# FlexEMG_v0r0_SF2-COMM.net
KiCad netlist of a schematic drawn in Altium Designer
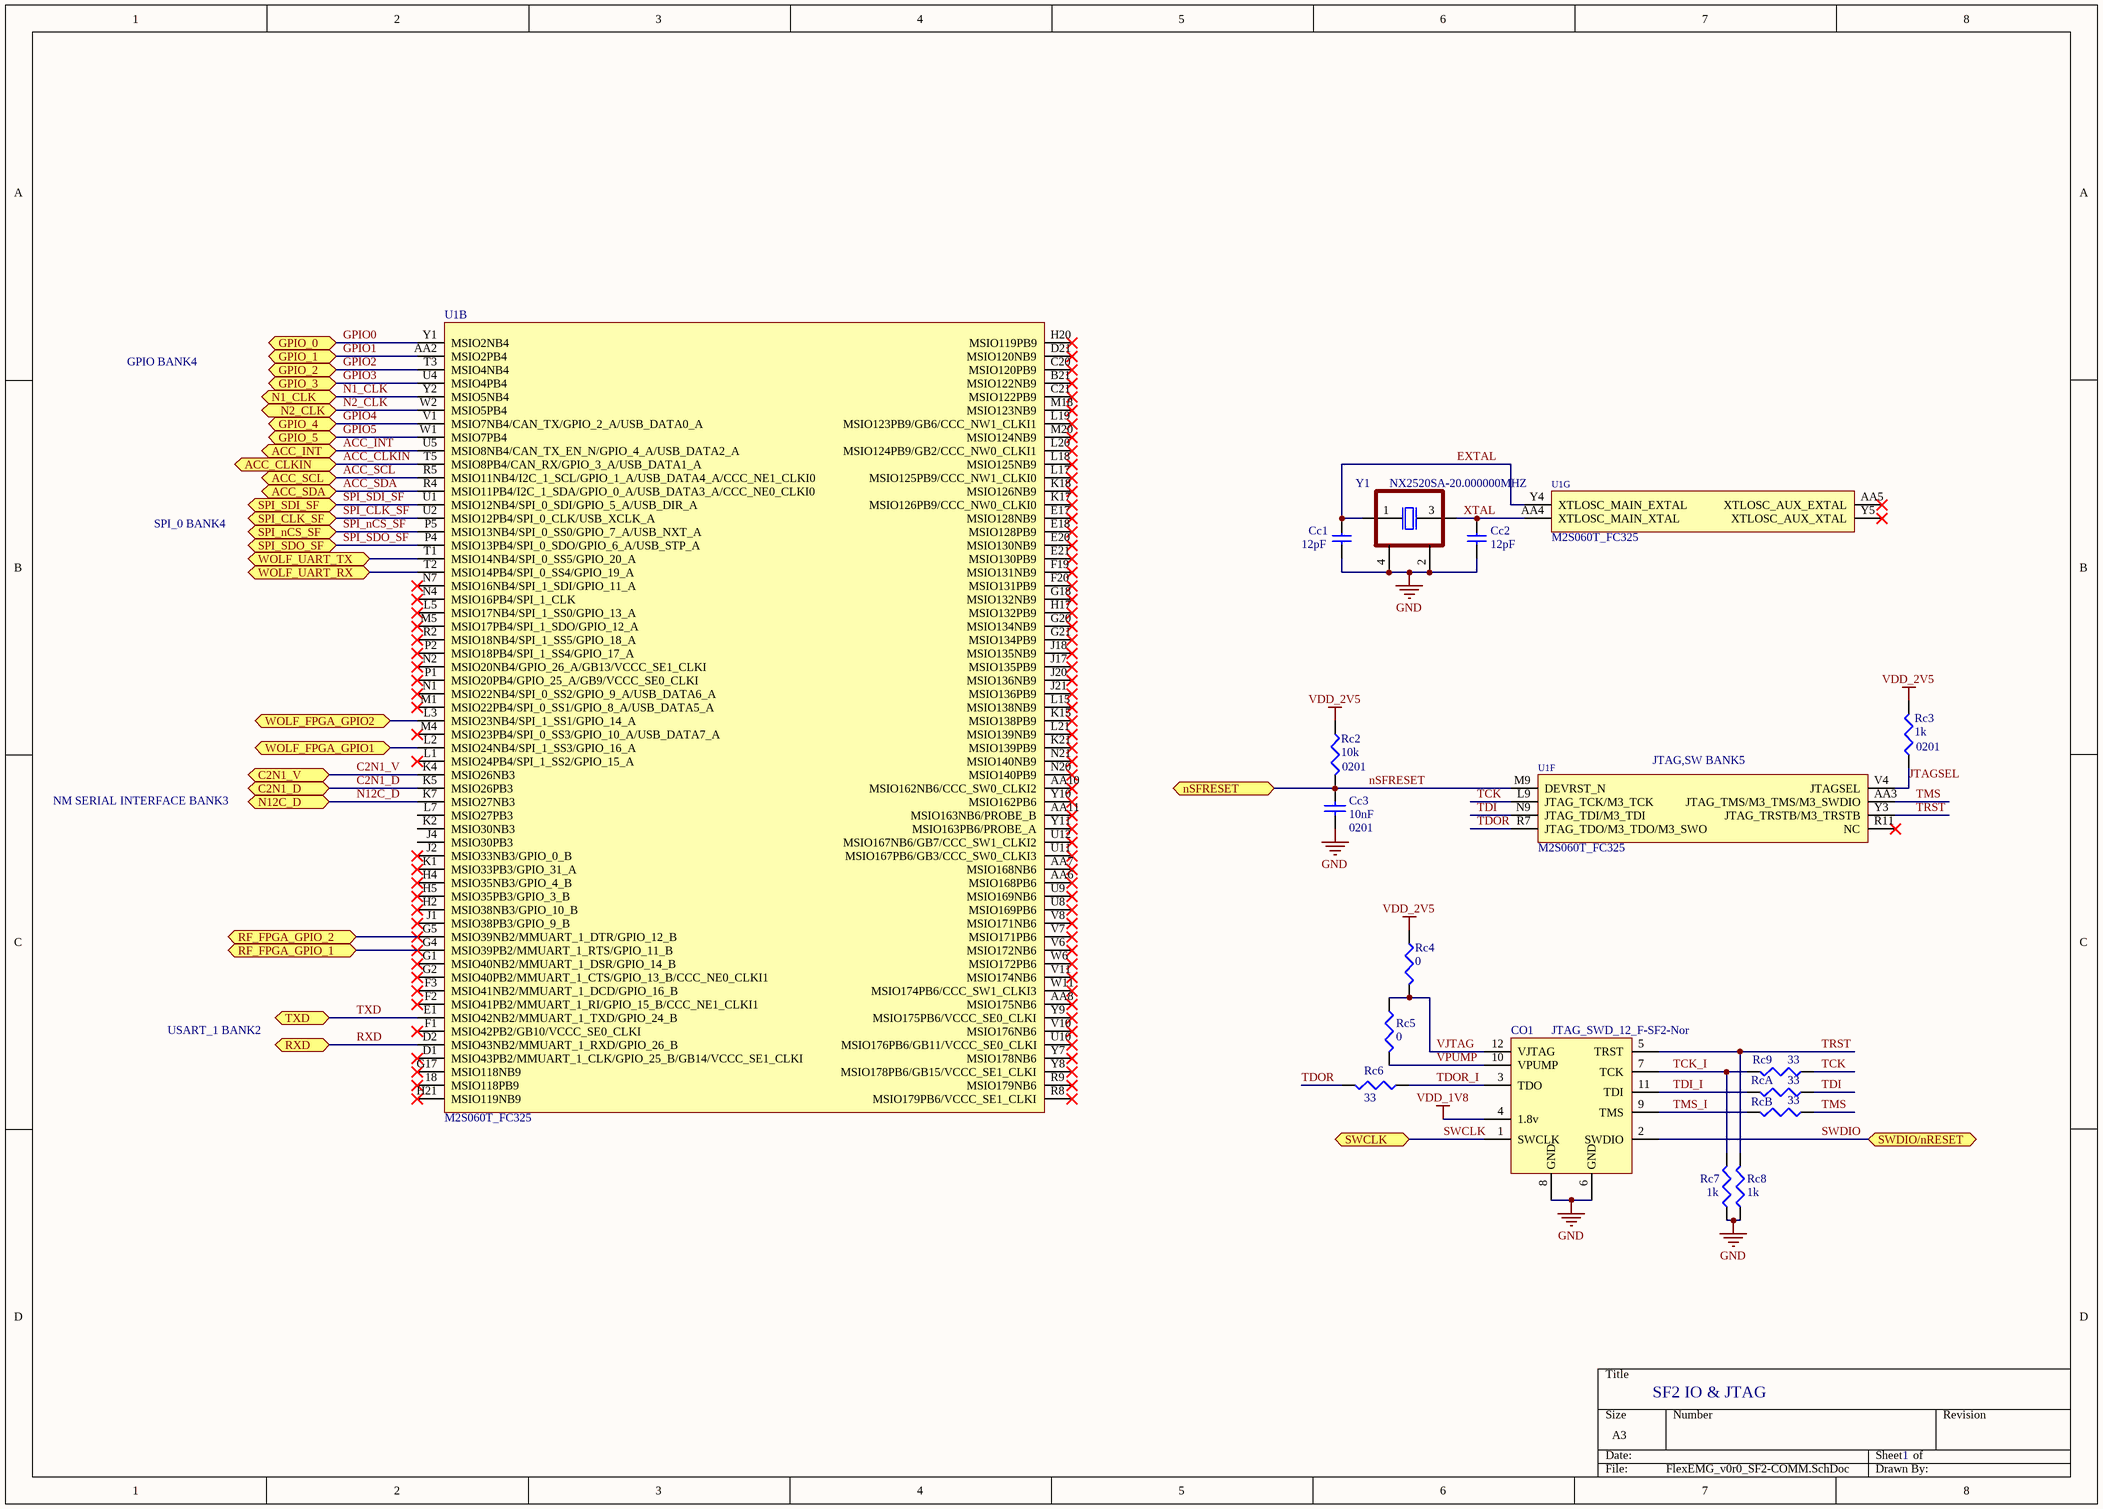
[diagram p0: FlexEMG_v0r0_SF2-COMM.SchDoc]

(export (version "E")
  (design (tool "Eeschema 10.0.6"))
  (components
    (comp (ref "Cc1")
      (value "12pF")
      (footprint "c0402-Murata-GR")
      (description "CAP CER 12PF 50V NP0 0402")
      (fields (field (name "MANUFACTURER") "Murata") (field (name "Comment") "GRM1555C1H120FA01D"))
      (libsource (lib "Custom") (part "CAP_0402"))
    )
    (comp (ref "Cc2")
      (value "12pF")
      (footprint "c0402-Murata-GR")
      (description "CAP CER 12PF 50V NP0 0402")
      (fields (field (name "MANUFACTURER") "Murata") (field (name "Comment") "GRM1555C1H120FA01D"))
      (libsource (lib "Custom") (part "CAP_0402"))
    )
    (comp (ref "Cc3")
      (value "0201")
      (footprint "c0201-Murata-GR")
      (description "CAP CER 10000PF 25V X5R 0201")
      (fields (field (name "ALTIUM_VALUE") "10nF") (field (name "MANUFACTURER") "Murata"))
      (libsource (lib "Custom") (part "Cap"))
    )
    (comp (ref "CO1")
      (value "JTAG_SWD_12_F-SF2-Nor")
      (footprint "CONN_12-CLP")
      (description "12 pin female JTAG/SWD header for SmartFusion2 and Nordic")
      (fields (field (name "MANUFACTURER") "Samtec"))
      (libsource (lib "CM") (part "JTAG_SWD_12_F-SF2-Nor"))
    )
    (comp (ref "Rc2")
      (value "10k")
      (footprint "0201_p")
      (description "RES SMD 10K OHM 1% 1/20W 0201")
      (fields
        (field (name "MANUFACTURER") "Panasonic")
        (field (name "POWER") "1/20W")
        (field (name "PACKAGE") "0201")
      )
      (libsource (lib "Custom") (part "Resistor"))
    )
    (comp (ref "Rc3")
      (value "1k")
      (footprint "0201_p")
      (description "RES SMD 1K OHM 1% 1/20W 0201")
      (fields
        (field (name "MANUFACTURER") "Panasonic")
        (field (name "POWER") "1/20W")
        (field (name "PACKAGE") "0201")
      )
      (libsource (lib "Custom") (part "Resistor"))
    )
    (comp (ref "Rc4")
      (value "0")
      (footprint "0402_p")
      (description "RES SMD 0.0OHM JUMPER 1/10W 0402")
      (fields (field (name "MANUFACTURER") "Panasonic") (field (name "POWER") "1/10W"))
      (libsource (lib "Custom") (part "Resistor"))
    )
    (comp (ref "Rc5")
      (value "0")
      (footprint "0402_p")
      (description "RES SMD 0.0OHM JUMPER 1/10W 0402")
      (fields (field (name "MANUFACTURER") "Panasonic") (field (name "POWER") "1/10W"))
      (libsource (lib "Custom") (part "Resistor"))
    )
    (comp (ref "Rc6")
      (value "33")
      (footprint "0402_p")
      (description "RES SMD 33 OHM 1% 1/10W 0402")
      (fields (field (name "MANUFACTURER") "Panasonic") (field (name "POWER") "1/5W"))
      (libsource (lib "Custom") (part "Resistor"))
    )
    (comp (ref "Rc7")
      (value "1k")
      (footprint "0402_p")
      (description "RES SMD 1K OHM 1% 1/10W 0402")
      (fields (field (name "MANUFACTURER") "Panasonic") (field (name "POWER") "1/10W"))
      (libsource (lib "Custom") (part "Resistor"))
    )
    (comp (ref "Rc8")
      (value "1k")
      (footprint "0402_p")
      (description "RES SMD 1K OHM 1% 1/10W 0402")
      (fields (field (name "MANUFACTURER") "Panasonic") (field (name "POWER") "1/10W"))
      (libsource (lib "Custom") (part "Resistor"))
    )
    (comp (ref "Rc9")
      (value "33")
      (footprint "0402_p")
      (description "RES SMD 33 OHM 1% 1/10W 0402")
      (fields (field (name "MANUFACTURER") "Panasonic") (field (name "POWER") "1/5W"))
      (libsource (lib "Custom") (part "Resistor"))
    )
    (comp (ref "RcA")
      (value "33")
      (footprint "0402_p")
      (description "RES SMD 33 OHM 1% 1/10W 0402")
      (fields (field (name "MANUFACTURER") "Panasonic") (field (name "POWER") "1/5W"))
      (libsource (lib "Custom") (part "Resistor"))
    )
    (comp (ref "RcB")
      (value "33")
      (footprint "0402_p")
      (description "RES SMD 33 OHM 1% 1/10W 0402")
      (fields (field (name "MANUFACTURER") "Panasonic") (field (name "POWER") "1/5W"))
      (libsource (lib "Custom") (part "Resistor"))
    )
    (comp (ref "U1")
      (value "M2S060T_FC325")
      (footprint "MCSM-CS-325")
      (description "SmartFusion2")
      (fields (field (name "MANUFACTURER") "Microsemi"))
      (libsource (lib "CM") (part "M2S060T_FC325"))
    )
    (comp (ref "Y1")
      (value "NX2520SA-20.000000MHZ")
      (footprint "XOSC_4PIN")
      (description "CRYSTAL 20.0000MHZ 10PF SMD")
      (fields (field (name "MANUFACTURER") "NDK"))
      (libsource (lib "CM") (part "XOSC"))
    )
  )
  (nets
    (net (code "1") (name "/ACC_CLKIN") (class "Default")
      (node (ref "U1") (pin "T5") (pinfunction "MSIO8PB4/CAN_RX/GPIO_3_A/USB_DATA1_A_T5") (pintype "passive"))
    )
    (net (code "2") (name "/ACC_INT") (class "Default")
      (node (ref "U1") (pin "U5") (pinfunction "MSIO8NB4/CAN_TX_EN_N/GPIO_4_A/USB_DATA2_A_U5") (pintype "passive"))
    )
    (net (code "3") (name "/ACC_SCL") (class "Default")
      (node (ref "U1") (pin "R5") (pinfunction "MSIO11NB4/I2C_1_SCL/GPIO_1_A/USB_DATA4_A/CCC_NE1_CLKI0_R5") (pintype "passive"))
    )
    (net (code "4") (name "/ACC_SDA") (class "Default")
      (node (ref "U1") (pin "R4") (pinfunction "MSIO11PB4/I2C_1_SDA/GPIO_0_A/USB_DATA3_A/CCC_NE0_CLKI0_R4") (pintype "passive"))
    )
    (net (code "5") (name "/C2N1_D") (class "Default")
      (node (ref "U1") (pin "K5") (pinfunction "MSIO26PB3_K5") (pintype "passive"))
    )
    (net (code "6") (name "/C2N1_V") (class "Default")
      (node (ref "U1") (pin "K4") (pinfunction "MSIO26NB3_K4") (pintype "passive"))
    )
    (net (code "7") (name "/EXTAL") (class "Default")
      (node (ref "Cc1") (pin "2") (pinfunction "2_2") (pintype "passive"))
      (node (ref "U1") (pin "Y4") (pinfunction "XTLOSC_MAIN_EXTAL_Y4") (pintype "passive"))
      (node (ref "Y1") (pin "1") (pinfunction "inp_1") (pintype "passive"))
    )
    (net (code "8") (name "/GPIO0") (class "Default")
      (node (ref "U1") (pin "Y1") (pinfunction "MSIO2NB4_Y1") (pintype "passive"))
    )
    (net (code "9") (name "/GPIO1") (class "Default")
      (node (ref "U1") (pin "AA2") (pinfunction "MSIO2PB4_AA2") (pintype "passive"))
    )
    (net (code "10") (name "/GPIO2") (class "Default")
      (node (ref "U1") (pin "T3") (pinfunction "MSIO4NB4_T3") (pintype "passive"))
    )
    (net (code "11") (name "/GPIO3") (class "Default")
      (node (ref "U1") (pin "U4") (pinfunction "MSIO4PB4_U4") (pintype "passive"))
    )
    (net (code "12") (name "/GPIO4") (class "Default")
      (node (ref "U1") (pin "V1") (pinfunction "MSIO7NB4/CAN_TX/GPIO_2_A/USB_DATA0_A_V1") (pintype "passive"))
    )
    (net (code "13") (name "/GPIO5") (class "Default")
      (node (ref "U1") (pin "W1") (pinfunction "MSIO7PB4_W1") (pintype "passive"))
    )
    (net (code "14") (name "/JTAGSEL") (class "Default")
      (node (ref "Rc3") (pin "1") (pinfunction "1_1") (pintype "passive"))
      (node (ref "U1") (pin "V4") (pinfunction "JTAGSEL_V4") (pintype "passive"))
    )
    (net (code "15") (name "/N1_CLK") (class "Default")
      (node (ref "U1") (pin "Y2") (pinfunction "MSIO5NB4_Y2") (pintype "passive"))
    )
    (net (code "16") (name "/N2_CLK") (class "Default")
      (node (ref "U1") (pin "W2") (pinfunction "MSIO5PB4_W2") (pintype "passive"))
    )
    (net (code "17") (name "/N12C_D") (class "Default")
      (node (ref "U1") (pin "K7") (pinfunction "MSIO27NB3_K7") (pintype "passive"))
    )
    (net (code "18") (name "/RF_FPGA_GPIO_1") (class "Default")
      (node (ref "U1") (pin "G4") (pinfunction "MSIO39PB2/MMUART_1_RTS/GPIO_11_B_G4") (pintype "passive+no_connect"))
    )
    (net (code "19") (name "/RF_FPGA_GPIO_2") (class "Default")
      (node (ref "U1") (pin "G5") (pinfunction "MSIO39NB2/MMUART_1_DTR/GPIO_12_B_G5") (pintype "passive+no_connect"))
    )
    (net (code "20") (name "/RXD") (class "Default")
      (node (ref "U1") (pin "D2") (pinfunction "MSIO43NB2/MMUART_1_RXD/GPIO_26_B_D2") (pintype "passive"))
    )
    (net (code "21") (name "/SPI_CLK_SF") (class "Default")
      (node (ref "U1") (pin "U2") (pinfunction "MSIO12PB4/SPI_0_CLK/USB_XCLK_A_U2") (pintype "passive"))
    )
    (net (code "22") (name "/SPI_SDI_SF") (class "Default")
      (node (ref "U1") (pin "U1") (pinfunction "MSIO12NB4/SPI_0_SDI/GPIO_5_A/USB_DIR_A_U1") (pintype "passive"))
    )
    (net (code "23") (name "/SPI_SDO_SF") (class "Default")
      (node (ref "U1") (pin "P4") (pinfunction "MSIO13PB4/SPI_0_SDO/GPIO_6_A/USB_STP_A_P4") (pintype "passive"))
    )
    (net (code "24") (name "/SPI_nCS_SF") (class "Default")
      (node (ref "U1") (pin "P5") (pinfunction "MSIO13NB4/SPI_0_SS0/GPIO_7_A/USB_NXT_A_P5") (pintype "passive"))
    )
    (net (code "25") (name "/SWCLK") (class "Default")
      (node (ref "CO1") (pin "1") (pinfunction "SWCLK_1") (pintype "passive"))
    )
    (net (code "26") (name "/SWDIO") (class "Default")
      (node (ref "CO1") (pin "2") (pinfunction "SWDIO_2") (pintype "passive"))
    )
    (net (code "27") (name "/TCK") (class "Default")
      (node (ref "Rc9") (pin "1") (pinfunction "1_1") (pintype "passive"))
      (node (ref "U1") (pin "L9") (pinfunction "JTAG_TCK/M3_TCK_L9") (pintype "passive"))
    )
    (net (code "28") (name "/TCK_I") (class "Default")
      (node (ref "CO1") (pin "7") (pinfunction "TCK_7") (pintype "passive"))
      (node (ref "Rc7") (pin "2") (pinfunction "2_2") (pintype "passive"))
      (node (ref "Rc9") (pin "2") (pinfunction "2_2") (pintype "passive"))
    )
    (net (code "29") (name "/TDI") (class "Default")
      (node (ref "RcA") (pin "1") (pinfunction "1_1") (pintype "passive"))
      (node (ref "U1") (pin "N9") (pinfunction "JTAG_TDI/M3_TDI_N9") (pintype "passive"))
    )
    (net (code "30") (name "/TDI_I") (class "Default")
      (node (ref "CO1") (pin "11") (pinfunction "TDI_11") (pintype "passive"))
      (node (ref "RcA") (pin "2") (pinfunction "2_2") (pintype "passive"))
    )
    (net (code "31") (name "/TDOR") (class "Default")
      (node (ref "Rc6") (pin "2") (pinfunction "2_2") (pintype "passive"))
      (node (ref "U1") (pin "R7") (pinfunction "JTAG_TDO/M3_TDO/M3_SWO_R7") (pintype "passive"))
    )
    (net (code "32") (name "/TDOR_I") (class "Default")
      (node (ref "CO1") (pin "3") (pinfunction "TDO_3") (pintype "passive"))
      (node (ref "Rc6") (pin "1") (pinfunction "1_1") (pintype "passive"))
    )
    (net (code "33") (name "/TMS") (class "Default")
      (node (ref "RcB") (pin "1") (pinfunction "1_1") (pintype "passive"))
      (node (ref "U1") (pin "AA3") (pinfunction "JTAG_TMS/M3_TMS/M3_SWDIO_AA3") (pintype "passive"))
    )
    (net (code "34") (name "/TMS_I") (class "Default")
      (node (ref "CO1") (pin "9") (pinfunction "TMS_9") (pintype "passive"))
      (node (ref "RcB") (pin "2") (pinfunction "2_2") (pintype "passive"))
    )
    (net (code "35") (name "/TRST") (class "Default")
      (node (ref "CO1") (pin "5") (pinfunction "TRST_5") (pintype "passive"))
      (node (ref "Rc8") (pin "2") (pinfunction "2_2") (pintype "passive"))
      (node (ref "U1") (pin "Y3") (pinfunction "JTAG_TRSTB/M3_TRSTB_Y3") (pintype "passive"))
    )
    (net (code "36") (name "/TXD") (class "Default")
      (node (ref "U1") (pin "E1") (pinfunction "MSIO42NB2/MMUART_1_TXD/GPIO_24_B_E1") (pintype "passive"))
    )
    (net (code "37") (name "/VJTAG") (class "Default")
      (node (ref "CO1") (pin "12") (pinfunction "VJTAG_12") (pintype "power_in"))
      (node (ref "Rc4") (pin "2") (pinfunction "2_2") (pintype "passive"))
      (node (ref "Rc5") (pin "1") (pinfunction "1_1") (pintype "passive"))
    )
    (net (code "38") (name "/VPUMP") (class "Default")
      (node (ref "CO1") (pin "10") (pinfunction "VPUMP_10") (pintype "power_in"))
      (node (ref "Rc5") (pin "2") (pinfunction "2_2") (pintype "passive"))
    )
    (net (code "39") (name "/WOLF_FPGA_GPIO1") (class "Default")
      (node (ref "U1") (pin "L2") (pinfunction "MSIO24NB4/SPI_1_SS3/GPIO_16_A_L2") (pintype "passive"))
    )
    (net (code "40") (name "/WOLF_FPGA_GPIO2") (class "Default")
      (node (ref "U1") (pin "L3") (pinfunction "MSIO23NB4/SPI_1_SS1/GPIO_14_A_L3") (pintype "passive"))
    )
    (net (code "41") (name "/WOLF_UART_RX") (class "Default")
      (node (ref "U1") (pin "T2") (pinfunction "MSIO14PB4/SPI_0_SS4/GPIO_19_A_T2") (pintype "passive"))
    )
    (net (code "42") (name "/WOLF_UART_TX") (class "Default")
      (node (ref "U1") (pin "T1") (pinfunction "MSIO14NB4/SPI_0_SS5/GPIO_20_A_T1") (pintype "passive"))
    )
    (net (code "43") (name "/XTAL") (class "Default")
      (node (ref "Cc2") (pin "2") (pinfunction "2_2") (pintype "passive"))
      (node (ref "U1") (pin "AA4") (pinfunction "XTLOSC_MAIN_XTAL_AA4") (pintype "passive"))
      (node (ref "Y1") (pin "3") (pinfunction "out_3") (pintype "passive"))
    )
    (net (code "44") (name "/nSFRESET") (class "Default")
      (node (ref "Cc3") (pin "2") (pinfunction "2_2") (pintype "passive"))
      (node (ref "Rc2") (pin "2") (pinfunction "2_2") (pintype "passive"))
      (node (ref "U1") (pin "M9") (pinfunction "DEVRST_N_M9") (pintype "passive"))
    )
    (net (code "45") (name "GND") (class "Default")
      (node (ref "CO1") (pin "6") (pinfunction "GND_6") (pintype "power_in"))
      (node (ref "CO1") (pin "8") (pinfunction "GND_8") (pintype "power_in"))
      (node (ref "Cc1") (pin "1") (pinfunction "1_1") (pintype "passive"))
      (node (ref "Cc2") (pin "1") (pinfunction "1_1") (pintype "passive"))
      (node (ref "Cc3") (pin "1") (pinfunction "1_1") (pintype "passive"))
      (node (ref "Rc7") (pin "1") (pinfunction "1_1") (pintype "passive"))
      (node (ref "Rc8") (pin "1") (pinfunction "1_1") (pintype "passive"))
      (node (ref "Y1") (pin "2") (pinfunction "GND_2") (pintype "passive"))
      (node (ref "Y1") (pin "4") (pinfunction "GND_4") (pintype "passive"))
    )
    (net (code "46") (name "VDD_1V8") (class "Default")
      (node (ref "CO1") (pin "4") (pinfunction "1.8v_4") (pintype "passive"))
    )
    (net (code "47") (name "VDD_2V5") (class "Default")
      (node (ref "Rc2") (pin "1") (pinfunction "1_1") (pintype "passive"))
      (node (ref "Rc3") (pin "2") (pinfunction "2_2") (pintype "passive"))
      (node (ref "Rc4") (pin "1") (pinfunction "1_1") (pintype "passive"))
    )
    (net (code "48") (name "unconnected-(U1B-MSIO16NB4{slash}SPI_1_SDI{slash}GPIO_11_A-PadN7)") (class "Default")
      (node (ref "U1") (pin "N7") (pinfunction "MSIO16NB4/SPI_1_SDI/GPIO_11_A_N7") (pintype "passive+no_connect"))
    )
    (net (code "49") (name "unconnected-(U1B-MSIO16PB4{slash}SPI_1_CLK-PadN4)") (class "Default")
      (node (ref "U1") (pin "N4") (pinfunction "MSIO16PB4/SPI_1_CLK_N4") (pintype "passive+no_connect"))
    )
    (net (code "50") (name "unconnected-(U1B-MSIO17NB4{slash}SPI_1_SS0{slash}GPIO_13_A-PadL5)") (class "Default")
      (node (ref "U1") (pin "L5") (pinfunction "MSIO17NB4/SPI_1_SS0/GPIO_13_A_L5") (pintype "passive+no_connect"))
    )
    (net (code "51") (name "unconnected-(U1B-MSIO17PB4{slash}SPI_1_SDO{slash}GPIO_12_A-PadM5)") (class "Default")
      (node (ref "U1") (pin "M5") (pinfunction "MSIO17PB4/SPI_1_SDO/GPIO_12_A_M5") (pintype "passive+no_connect"))
    )
    (net (code "52") (name "unconnected-(U1B-MSIO18NB4{slash}SPI_1_SS5{slash}GPIO_18_A-PadR2)") (class "Default")
      (node (ref "U1") (pin "R2") (pinfunction "MSIO18NB4/SPI_1_SS5/GPIO_18_A_R2") (pintype "passive+no_connect"))
    )
    (net (code "53") (name "unconnected-(U1B-MSIO18PB4{slash}SPI_1_SS4{slash}GPIO_17_A-PadP2)") (class "Default")
      (node (ref "U1") (pin "P2") (pinfunction "MSIO18PB4/SPI_1_SS4/GPIO_17_A_P2") (pintype "passive+no_connect"))
    )
    (net (code "54") (name "unconnected-(U1B-MSIO20NB4{slash}GPIO_26_A{slash}GB13{slash}VCCC_SE1_CLKI-PadN2)") (class "Default")
      (node (ref "U1") (pin "N2") (pinfunction "MSIO20NB4/GPIO_26_A/GB13/VCCC_SE1_CLKI_N2") (pintype "passive+no_connect"))
    )
    (net (code "55") (name "unconnected-(U1B-MSIO20PB4{slash}GPIO_25_A{slash}GB9{slash}VCCC_SE0_CLKI-PadP1)") (class "Default")
      (node (ref "U1") (pin "P1") (pinfunction "MSIO20PB4/GPIO_25_A/GB9/VCCC_SE0_CLKI_P1") (pintype "passive+no_connect"))
    )
    (net (code "56") (name "unconnected-(U1B-MSIO22NB4{slash}SPI_0_SS2{slash}GPIO_9_A{slash}USB_DATA6_A-PadN1)") (class "Default")
      (node (ref "U1") (pin "N1") (pinfunction "MSIO22NB4/SPI_0_SS2/GPIO_9_A/USB_DATA6_A_N1") (pintype "passive+no_connect"))
    )
    (net (code "57") (name "unconnected-(U1B-MSIO22PB4{slash}SPI_0_SS1{slash}GPIO_8_A{slash}USB_DATA5_A-PadM1)") (class "Default")
      (node (ref "U1") (pin "M1") (pinfunction "MSIO22PB4/SPI_0_SS1/GPIO_8_A/USB_DATA5_A_M1") (pintype "passive+no_connect"))
    )
    (net (code "58") (name "unconnected-(U1B-MSIO23PB4{slash}SPI_0_SS3{slash}GPIO_10_A{slash}USB_DATA7_A-PadM4)") (class "Default")
      (node (ref "U1") (pin "M4") (pinfunction "MSIO23PB4/SPI_0_SS3/GPIO_10_A/USB_DATA7_A_M4") (pintype "passive+no_connect"))
    )
    (net (code "59") (name "unconnected-(U1B-MSIO24PB4{slash}SPI_1_SS2{slash}GPIO_15_A-PadL1)") (class "Default")
      (node (ref "U1") (pin "L1") (pinfunction "MSIO24PB4/SPI_1_SS2/GPIO_15_A_L1") (pintype "passive+no_connect"))
    )
    (net (code "60") (name "unconnected-(U1B-MSIO27PB3-PadL7)") (class "Default")
      (node (ref "U1") (pin "L7") (pinfunction "MSIO27PB3_L7") (pintype "passive"))
    )
    (net (code "61") (name "unconnected-(U1B-MSIO30NB3-PadK2)") (class "Default")
      (node (ref "U1") (pin "K2") (pinfunction "MSIO30NB3_K2") (pintype "passive"))
    )
    (net (code "62") (name "unconnected-(U1B-MSIO30PB3-PadJ4)") (class "Default")
      (node (ref "U1") (pin "J4") (pinfunction "MSIO30PB3_J4") (pintype "passive"))
    )
    (net (code "63") (name "unconnected-(U1B-MSIO33NB3{slash}GPIO_0_B-PadJ2)") (class "Default")
      (node (ref "U1") (pin "J2") (pinfunction "MSIO33NB3/GPIO_0_B_J2") (pintype "passive+no_connect"))
    )
    (net (code "64") (name "unconnected-(U1B-MSIO33PB3{slash}GPIO_31_A-PadK1)") (class "Default")
      (node (ref "U1") (pin "K1") (pinfunction "MSIO33PB3/GPIO_31_A_K1") (pintype "passive+no_connect"))
    )
    (net (code "65") (name "unconnected-(U1B-MSIO35NB3{slash}GPIO_4_B-PadH4)") (class "Default")
      (node (ref "U1") (pin "H4") (pinfunction "MSIO35NB3/GPIO_4_B_H4") (pintype "passive+no_connect"))
    )
    (net (code "66") (name "unconnected-(U1B-MSIO35PB3{slash}GPIO_3_B-PadH5)") (class "Default")
      (node (ref "U1") (pin "H5") (pinfunction "MSIO35PB3/GPIO_3_B_H5") (pintype "passive+no_connect"))
    )
    (net (code "67") (name "unconnected-(U1B-MSIO38NB3{slash}GPIO_10_B-PadH2)") (class "Default")
      (node (ref "U1") (pin "H2") (pinfunction "MSIO38NB3/GPIO_10_B_H2") (pintype "passive+no_connect"))
    )
    (net (code "68") (name "unconnected-(U1B-MSIO38PB3{slash}GPIO_9_B-PadJ1)") (class "Default")
      (node (ref "U1") (pin "J1") (pinfunction "MSIO38PB3/GPIO_9_B_J1") (pintype "passive+no_connect"))
    )
    (net (code "69") (name "unconnected-(U1B-MSIO40NB2{slash}MMUART_1_DSR{slash}GPIO_14_B-PadG1)") (class "Default")
      (node (ref "U1") (pin "G1") (pinfunction "MSIO40NB2/MMUART_1_DSR/GPIO_14_B_G1") (pintype "passive+no_connect"))
    )
    (net (code "70") (name "unconnected-(U1B-MSIO40PB2{slash}MMUART_1_CTS{slash}GPIO_13_B{slash}CCC_NE0_CLKI1-PadG2)") (class "Default")
      (node (ref "U1") (pin "G2") (pinfunction "MSIO40PB2/MMUART_1_CTS/GPIO_13_B/CCC_NE0_CLKI1_G2") (pintype "passive+no_connect"))
    )
    (net (code "71") (name "unconnected-(U1B-MSIO41NB2{slash}MMUART_1_DCD{slash}GPIO_16_B-PadF3)") (class "Default")
      (node (ref "U1") (pin "F3") (pinfunction "MSIO41NB2/MMUART_1_DCD/GPIO_16_B_F3") (pintype "passive+no_connect"))
    )
    (net (code "72") (name "unconnected-(U1B-MSIO41PB2{slash}MMUART_1_RI{slash}GPIO_15_B{slash}CCC_NE1_CLKI1-PadF2)") (class "Default")
      (node (ref "U1") (pin "F2") (pinfunction "MSIO41PB2/MMUART_1_RI/GPIO_15_B/CCC_NE1_CLKI1_F2") (pintype "passive+no_connect"))
    )
    (net (code "73") (name "unconnected-(U1B-MSIO42PB2{slash}GB10{slash}VCCC_SE0_CLKI-PadF1)") (class "Default")
      (node (ref "U1") (pin "F1") (pinfunction "MSIO42PB2/GB10/VCCC_SE0_CLKI_F1") (pintype "passive+no_connect"))
    )
    (net (code "74") (name "unconnected-(U1B-MSIO43PB2{slash}MMUART_1_CLK{slash}GPIO_25_B{slash}GB14{slash}VCCC_SE1_CLKI-PadD1)") (class "Default")
      (node (ref "U1") (pin "D1") (pinfunction "MSIO43PB2/MMUART_1_CLK/GPIO_25_B/GB14/VCCC_SE1_CLKI_D1") (pintype "passive+no_connect"))
    )
    (net (code "75") (name "unconnected-(U1B-MSIO118NB9-PadG17)") (class "Default")
      (node (ref "U1") (pin "G17") (pinfunction "MSIO118NB9_G17") (pintype "passive+no_connect"))
    )
    (net (code "76") (name "unconnected-(U1B-MSIO118PB9-Pad18)") (class "Default")
      (node (ref "U1") (pin "18") (pinfunction "MSIO118PB9_18") (pintype "passive+no_connect"))
    )
    (net (code "77") (name "unconnected-(U1B-MSIO119NB9-PadH21)") (class "Default")
      (node (ref "U1") (pin "H21") (pinfunction "MSIO119NB9_H21") (pintype "passive+no_connect"))
    )
    (net (code "78") (name "unconnected-(U1B-MSIO119PB9-PadH20)") (class "Default")
      (node (ref "U1") (pin "H20") (pinfunction "MSIO119PB9_H20") (pintype "passive+no_connect"))
    )
    (net (code "79") (name "unconnected-(U1B-MSIO120NB9-PadD21)") (class "Default")
      (node (ref "U1") (pin "D21") (pinfunction "MSIO120NB9_D21") (pintype "passive+no_connect"))
    )
    (net (code "80") (name "unconnected-(U1B-MSIO120PB9-PadC20)") (class "Default")
      (node (ref "U1") (pin "C20") (pinfunction "MSIO120PB9_C20") (pintype "passive+no_connect"))
    )
    (net (code "81") (name "unconnected-(U1B-MSIO122NB9-PadB21)") (class "Default")
      (node (ref "U1") (pin "B21") (pinfunction "MSIO122NB9_B21") (pintype "passive+no_connect"))
    )
    (net (code "82") (name "unconnected-(U1B-MSIO122PB9-PadC21)") (class "Default")
      (node (ref "U1") (pin "C21") (pinfunction "MSIO122PB9_C21") (pintype "passive+no_connect"))
    )
    (net (code "83") (name "unconnected-(U1B-MSIO123NB9-PadM18)") (class "Default")
      (node (ref "U1") (pin "M18") (pinfunction "MSIO123NB9_M18") (pintype "passive+no_connect"))
    )
    (net (code "84") (name "unconnected-(U1B-MSIO123PB9{slash}GB6{slash}CCC_NW1_CLKI1-PadL19)") (class "Default")
      (node (ref "U1") (pin "L19") (pinfunction "MSIO123PB9/GB6/CCC_NW1_CLKI1_L19") (pintype "passive+no_connect"))
    )
    (net (code "85") (name "unconnected-(U1B-MSIO124NB9-PadM20)") (class "Default")
      (node (ref "U1") (pin "M20") (pinfunction "MSIO124NB9_M20") (pintype "passive+no_connect"))
    )
    (net (code "86") (name "unconnected-(U1B-MSIO124PB9{slash}GB2{slash}CCC_NW0_CLKI1-PadL20)") (class "Default")
      (node (ref "U1") (pin "L20") (pinfunction "MSIO124PB9/GB2/CCC_NW0_CLKI1_L20") (pintype "passive+no_connect"))
    )
    (net (code "87") (name "unconnected-(U1B-MSIO125NB9-PadL18)") (class "Default")
      (node (ref "U1") (pin "L18") (pinfunction "MSIO125NB9_L18") (pintype "passive+no_connect"))
    )
    (net (code "88") (name "unconnected-(U1B-MSIO125PB9{slash}CCC_NW1_CLKI0-PadL17)") (class "Default")
      (node (ref "U1") (pin "L17") (pinfunction "MSIO125PB9/CCC_NW1_CLKI0_L17") (pintype "passive+no_connect"))
    )
    (net (code "89") (name "unconnected-(U1B-MSIO126NB9-PadK18)") (class "Default")
      (node (ref "U1") (pin "K18") (pinfunction "MSIO126NB9_K18") (pintype "passive+no_connect"))
    )
    (net (code "90") (name "unconnected-(U1B-MSIO126PB9{slash}CCC_NW0_CLKI0-PadK17)") (class "Default")
      (node (ref "U1") (pin "K17") (pinfunction "MSIO126PB9/CCC_NW0_CLKI0_K17") (pintype "passive+no_connect"))
    )
    (net (code "91") (name "unconnected-(U1B-MSIO128NB9-PadE17)") (class "Default")
      (node (ref "U1") (pin "E17") (pinfunction "MSIO128NB9_E17") (pintype "passive+no_connect"))
    )
    (net (code "92") (name "unconnected-(U1B-MSIO128PB9-PadE18)") (class "Default")
      (node (ref "U1") (pin "E18") (pinfunction "MSIO128PB9_E18") (pintype "passive+no_connect"))
    )
    (net (code "93") (name "unconnected-(U1B-MSIO130NB9-PadE20)") (class "Default")
      (node (ref "U1") (pin "E20") (pinfunction "MSIO130NB9_E20") (pintype "passive+no_connect"))
    )
    (net (code "94") (name "unconnected-(U1B-MSIO130PB9-PadE21)") (class "Default")
      (node (ref "U1") (pin "E21") (pinfunction "MSIO130PB9_E21") (pintype "passive+no_connect"))
    )
    (net (code "95") (name "unconnected-(U1B-MSIO131NB9-PadF19)") (class "Default")
      (node (ref "U1") (pin "F19") (pinfunction "MSIO131NB9_F19") (pintype "passive+no_connect"))
    )
    (net (code "96") (name "unconnected-(U1B-MSIO131PB9-PadF20)") (class "Default")
      (node (ref "U1") (pin "F20") (pinfunction "MSIO131PB9_F20") (pintype "passive+no_connect"))
    )
    (net (code "97") (name "unconnected-(U1B-MSIO132NB9-PadG18)") (class "Default")
      (node (ref "U1") (pin "G18") (pinfunction "MSIO132NB9_G18") (pintype "passive+no_connect"))
    )
    (net (code "98") (name "unconnected-(U1B-MSIO132PB9-PadH17)") (class "Default")
      (node (ref "U1") (pin "H17") (pinfunction "MSIO132PB9_H17") (pintype "passive+no_connect"))
    )
    (net (code "99") (name "unconnected-(U1B-MSIO134NB9-PadG20)") (class "Default")
      (node (ref "U1") (pin "G20") (pinfunction "MSIO134NB9_G20") (pintype "passive+no_connect"))
    )
    (net (code "100") (name "unconnected-(U1B-MSIO134PB9-PadG21)") (class "Default")
      (node (ref "U1") (pin "G21") (pinfunction "MSIO134PB9_G21") (pintype "passive+no_connect"))
    )
    (net (code "101") (name "unconnected-(U1B-MSIO135NB9-PadJ18)") (class "Default")
      (node (ref "U1") (pin "J18") (pinfunction "MSIO135NB9_J18") (pintype "passive+no_connect"))
    )
    (net (code "102") (name "unconnected-(U1B-MSIO135PB9-PadJ17)") (class "Default")
      (node (ref "U1") (pin "J17") (pinfunction "MSIO135PB9_J17") (pintype "passive+no_connect"))
    )
    (net (code "103") (name "unconnected-(U1B-MSIO136NB9-PadJ20)") (class "Default")
      (node (ref "U1") (pin "J20") (pinfunction "MSIO136NB9_J20") (pintype "passive+no_connect"))
    )
    (net (code "104") (name "unconnected-(U1B-MSIO136PB9-PadJ21)") (class "Default")
      (node (ref "U1") (pin "J21") (pinfunction "MSIO136PB9_J21") (pintype "passive+no_connect"))
    )
    (net (code "105") (name "unconnected-(U1B-MSIO138NB9-PadL15)") (class "Default")
      (node (ref "U1") (pin "L15") (pinfunction "MSIO138NB9_L15") (pintype "passive+no_connect"))
    )
    (net (code "106") (name "unconnected-(U1B-MSIO138PB9-PadK15)") (class "Default")
      (node (ref "U1") (pin "K15") (pinfunction "MSIO138PB9_K15") (pintype "passive+no_connect"))
    )
    (net (code "107") (name "unconnected-(U1B-MSIO139NB9-PadL21)") (class "Default")
      (node (ref "U1") (pin "L21") (pinfunction "MSIO139NB9_L21") (pintype "passive+no_connect"))
    )
    (net (code "108") (name "unconnected-(U1B-MSIO139PB9-PadK21)") (class "Default")
      (node (ref "U1") (pin "K21") (pinfunction "MSIO139PB9_K21") (pintype "passive+no_connect"))
    )
    (net (code "109") (name "unconnected-(U1B-MSIO140NB9-PadN21)") (class "Default")
      (node (ref "U1") (pin "N21") (pinfunction "MSIO140NB9_N21") (pintype "passive+no_connect"))
    )
    (net (code "110") (name "unconnected-(U1B-MSIO140PB9-PadN20)") (class "Default")
      (node (ref "U1") (pin "N20") (pinfunction "MSIO140PB9_N20") (pintype "passive+no_connect"))
    )
    (net (code "111") (name "unconnected-(U1B-MSIO162NB6{slash}CCC_SW0_CLKI2-PadAA10)") (class "Default")
      (node (ref "U1") (pin "AA10") (pinfunction "MSIO162NB6/CCC_SW0_CLKI2_AA10") (pintype "passive+no_connect"))
    )
    (net (code "112") (name "unconnected-(U1B-MSIO162PB6-PadY10)") (class "Default")
      (node (ref "U1") (pin "Y10") (pinfunction "MSIO162PB6_Y10") (pintype "passive+no_connect"))
    )
    (net (code "113") (name "unconnected-(U1B-MSIO163NB6{slash}PROBE_B-PadAA11)") (class "Default")
      (node (ref "U1") (pin "AA11") (pinfunction "MSIO163NB6/PROBE_B_AA11") (pintype "passive+no_connect"))
    )
    (net (code "114") (name "unconnected-(U1B-MSIO163PB6{slash}PROBE_A-PadY11)") (class "Default")
      (node (ref "U1") (pin "Y11") (pinfunction "MSIO163PB6/PROBE_A_Y11") (pintype "passive+no_connect"))
    )
    (net (code "115") (name "unconnected-(U1B-MSIO167NB6{slash}GB7{slash}CCC_SW1_CLKI2-PadU12)") (class "Default")
      (node (ref "U1") (pin "U12") (pinfunction "MSIO167NB6/GB7/CCC_SW1_CLKI2_U12") (pintype "passive+no_connect"))
    )
    (net (code "116") (name "unconnected-(U1B-MSIO167PB6{slash}GB3{slash}CCC_SW0_CLKI3-PadU11)") (class "Default")
      (node (ref "U1") (pin "U11") (pinfunction "MSIO167PB6/GB3/CCC_SW0_CLKI3_U11") (pintype "passive+no_connect"))
    )
    (net (code "117") (name "unconnected-(U1B-MSIO168NB6-PadAA7)") (class "Default")
      (node (ref "U1") (pin "AA7") (pinfunction "MSIO168NB6_AA7") (pintype "passive+no_connect"))
    )
    (net (code "118") (name "unconnected-(U1B-MSIO168PB6-PadAA6)") (class "Default")
      (node (ref "U1") (pin "AA6") (pinfunction "MSIO168PB6_AA6") (pintype "passive+no_connect"))
    )
    (net (code "119") (name "unconnected-(U1B-MSIO169NB6-PadU9)") (class "Default")
      (node (ref "U1") (pin "U9") (pinfunction "MSIO169NB6_U9") (pintype "passive+no_connect"))
    )
    (net (code "120") (name "unconnected-(U1B-MSIO169PB6-PadU8)") (class "Default")
      (node (ref "U1") (pin "U8") (pinfunction "MSIO169PB6_U8") (pintype "passive+no_connect"))
    )
    (net (code "121") (name "unconnected-(U1B-MSIO171NB6-PadV8)") (class "Default")
      (node (ref "U1") (pin "V8") (pinfunction "MSIO171NB6_V8") (pintype "passive+no_connect"))
    )
    (net (code "122") (name "unconnected-(U1B-MSIO171PB6-PadV7)") (class "Default")
      (node (ref "U1") (pin "V7") (pinfunction "MSIO171PB6_V7") (pintype "passive+no_connect"))
    )
    (net (code "123") (name "unconnected-(U1B-MSIO172NB6-PadV6)") (class "Default")
      (node (ref "U1") (pin "V6") (pinfunction "MSIO172NB6_V6") (pintype "passive+no_connect"))
    )
    (net (code "124") (name "unconnected-(U1B-MSIO172PB6-PadW6)") (class "Default")
      (node (ref "U1") (pin "W6") (pinfunction "MSIO172PB6_W6") (pintype "passive+no_connect"))
    )
    (net (code "125") (name "unconnected-(U1B-MSIO174NB6-PadV11)") (class "Default")
      (node (ref "U1") (pin "V11") (pinfunction "MSIO174NB6_V11") (pintype "passive+no_connect"))
    )
    (net (code "126") (name "unconnected-(U1B-MSIO174PB6{slash}CCC_SW1_CLKI3-PadW11)") (class "Default")
      (node (ref "U1") (pin "W11") (pinfunction "MSIO174PB6/CCC_SW1_CLKI3_W11") (pintype "passive+no_connect"))
    )
    (net (code "127") (name "unconnected-(U1B-MSIO175NB6-PadAA8)") (class "Default")
      (node (ref "U1") (pin "AA8") (pinfunction "MSIO175NB6_AA8") (pintype "passive+no_connect"))
    )
    (net (code "128") (name "unconnected-(U1B-MSIO175PB6{slash}VCCC_SE0_CLKI-PadY9)") (class "Default")
      (node (ref "U1") (pin "Y9") (pinfunction "MSIO175PB6/VCCC_SE0_CLKI_Y9") (pintype "passive+no_connect"))
    )
    (net (code "129") (name "unconnected-(U1B-MSIO176NB6-PadV10)") (class "Default")
      (node (ref "U1") (pin "V10") (pinfunction "MSIO176NB6_V10") (pintype "passive+no_connect"))
    )
    (net (code "130") (name "unconnected-(U1B-MSIO176PB6{slash}GB11{slash}VCCC_SE0_CLKI-PadU10)") (class "Default")
      (node (ref "U1") (pin "U10") (pinfunction "MSIO176PB6/GB11/VCCC_SE0_CLKI_U10") (pintype "passive+no_connect"))
    )
    (net (code "131") (name "unconnected-(U1B-MSIO178NB6-PadY7)") (class "Default")
      (node (ref "U1") (pin "Y7") (pinfunction "MSIO178NB6_Y7") (pintype "passive+no_connect"))
    )
    (net (code "132") (name "unconnected-(U1B-MSIO178PB6{slash}GB15{slash}VCCC_SE1_CLKI-PadY8)") (class "Default")
      (node (ref "U1") (pin "Y8") (pinfunction "MSIO178PB6/GB15/VCCC_SE1_CLKI_Y8") (pintype "passive+no_connect"))
    )
    (net (code "133") (name "unconnected-(U1B-MSIO179NB6-PadR9)") (class "Default")
      (node (ref "U1") (pin "R9") (pinfunction "MSIO179NB6_R9") (pintype "passive+no_connect"))
    )
    (net (code "134") (name "unconnected-(U1B-MSIO179PB6{slash}VCCC_SE1_CLKI-PadR8)") (class "Default")
      (node (ref "U1") (pin "R8") (pinfunction "MSIO179PB6/VCCC_SE1_CLKI_R8") (pintype "passive+no_connect"))
    )
    (net (code "135") (name "unconnected-(U1F-NC-PadR11)") (class "Default")
      (node (ref "U1") (pin "R11") (pinfunction "NC_R11") (pintype "passive+no_connect"))
    )
    (net (code "136") (name "unconnected-(U1G-XTLOSC_AUX_EXTAL-PadAA5)") (class "Default")
      (node (ref "U1") (pin "AA5") (pinfunction "XTLOSC_AUX_EXTAL_AA5") (pintype "passive+no_connect"))
    )
    (net (code "137") (name "unconnected-(U1G-XTLOSC_AUX_XTAL-PadY5)") (class "Default")
      (node (ref "U1") (pin "Y5") (pinfunction "XTLOSC_AUX_XTAL_Y5") (pintype "passive+no_connect"))
    )
  )
)
